# support_mega2560_pro_mini.net
KiCad netlist of a schematic drawn in EasyEDA
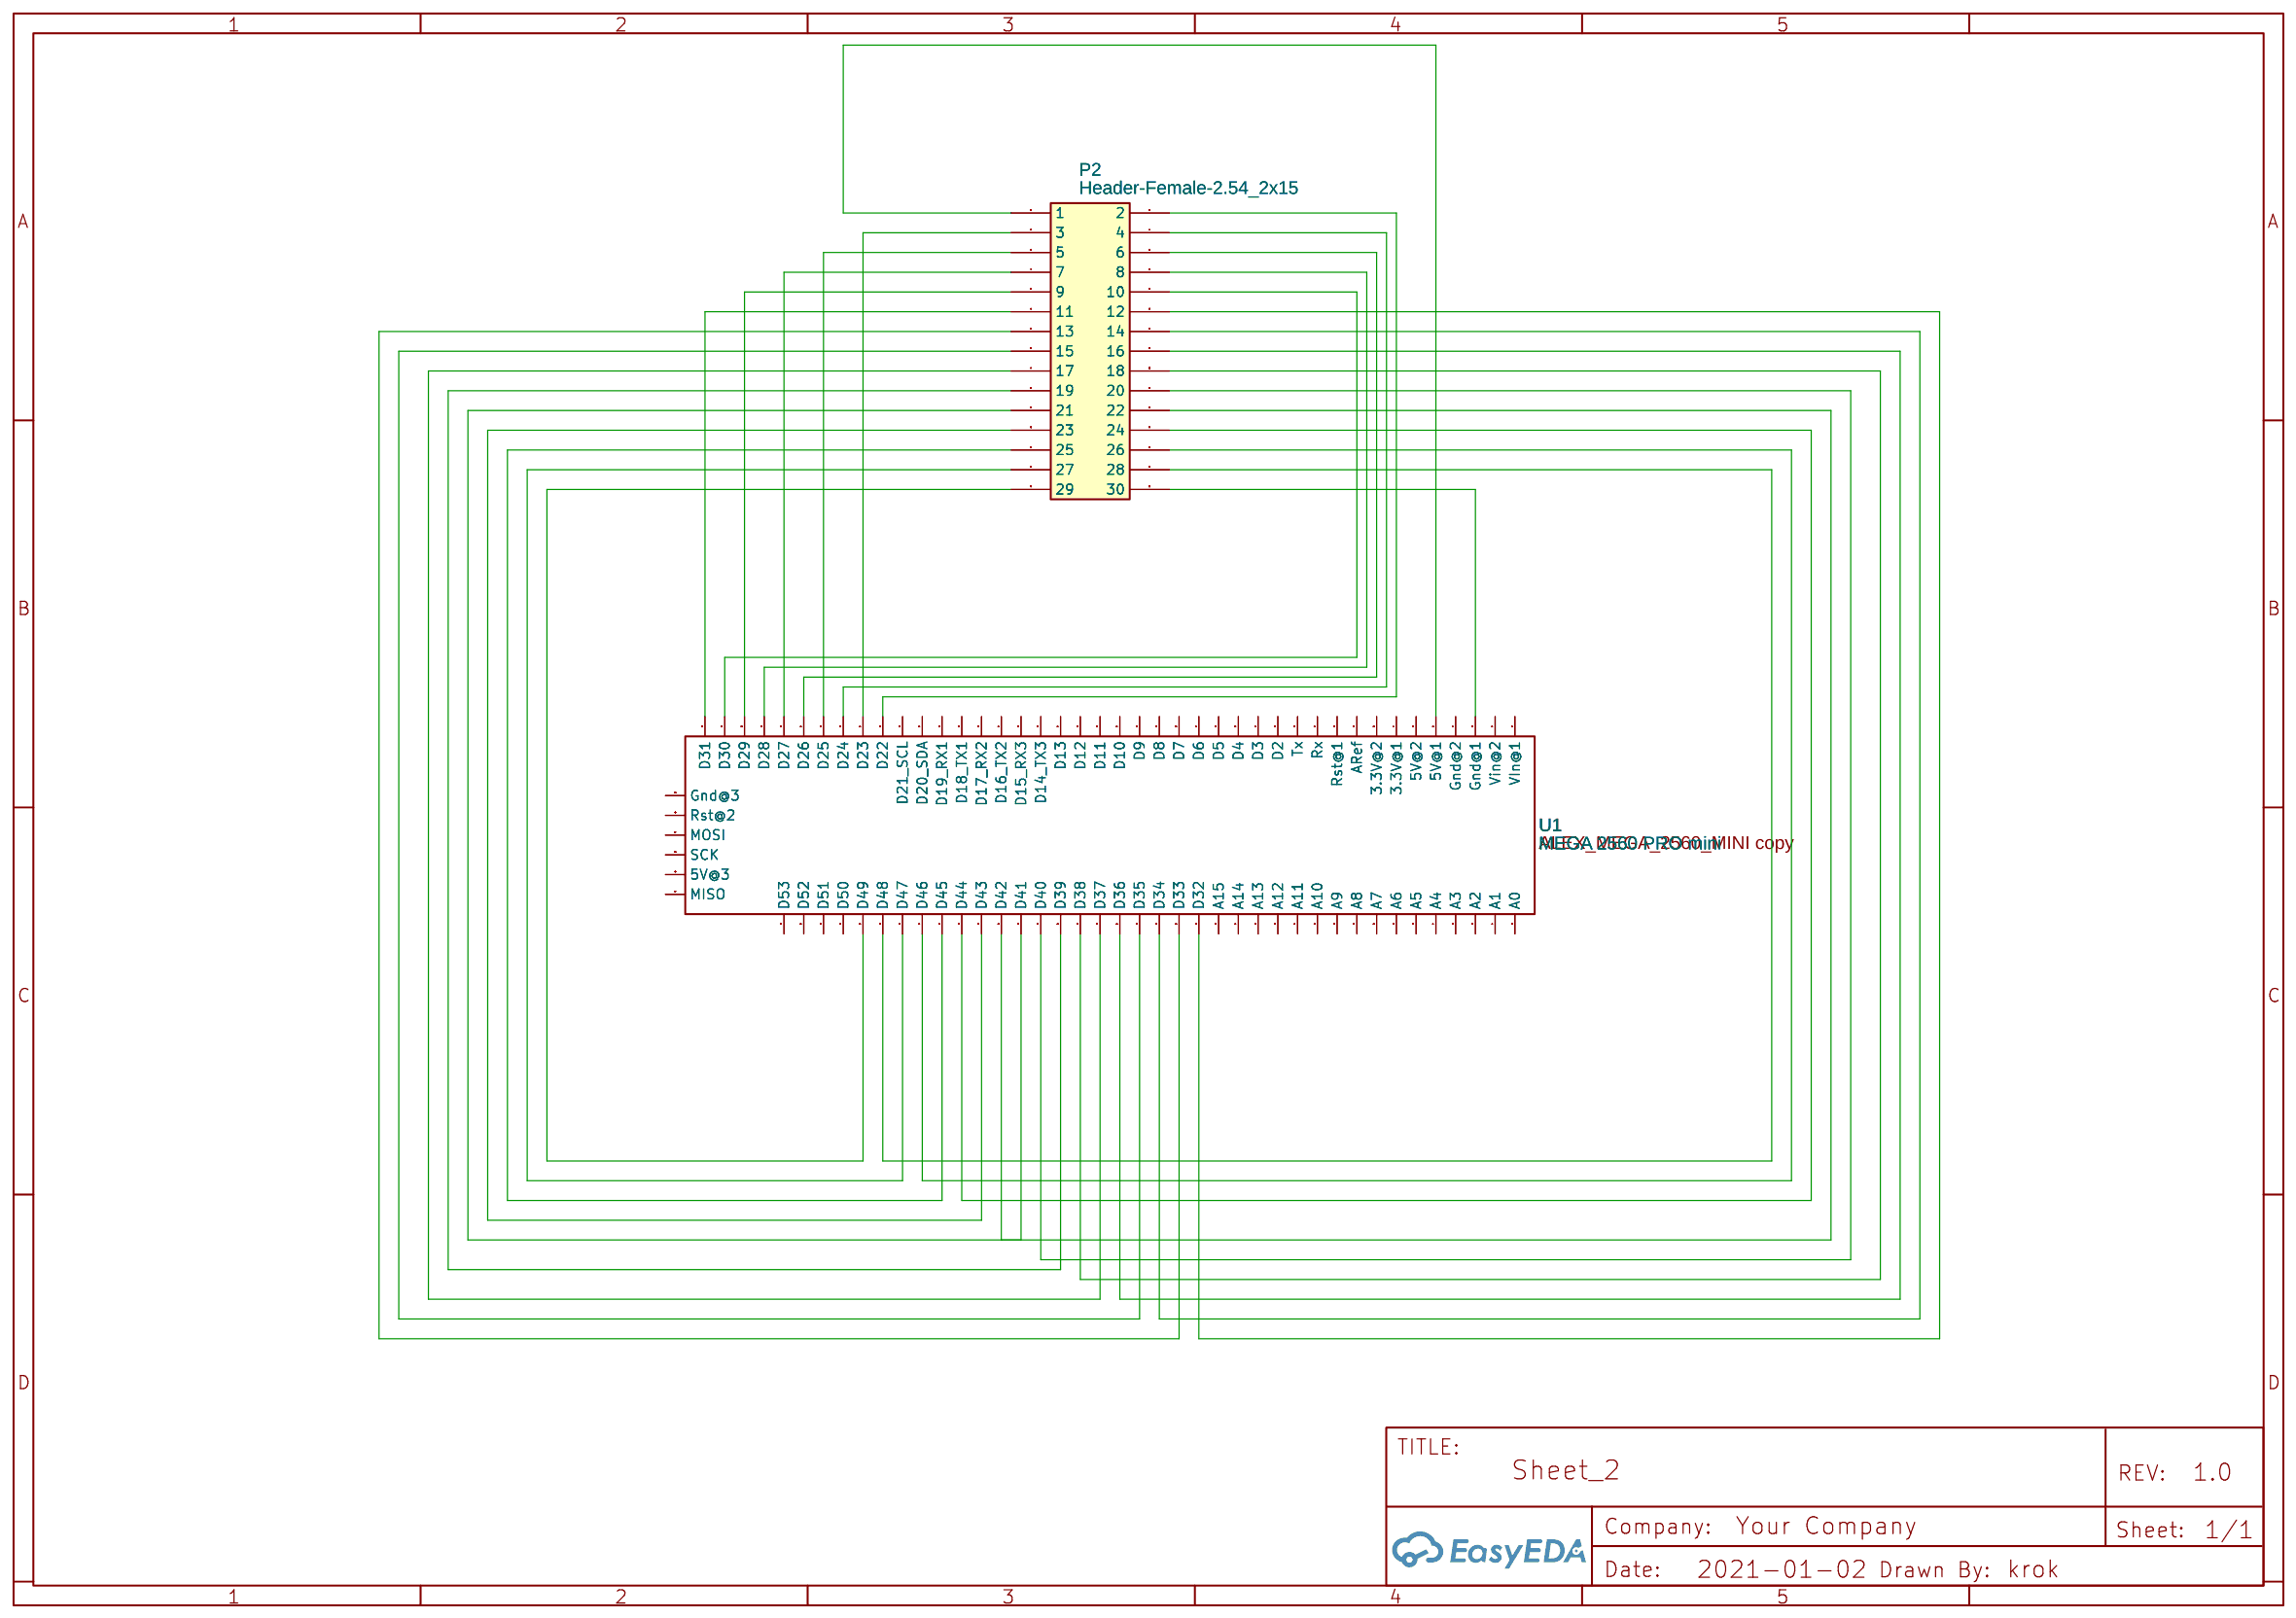
[diagram p0: schematic sheet]

(export (version "E")
  (design (tool "Eeschema 10.0.6"))
  (components
    (comp (ref "P2")
      (value "Header-Female-2.54_2x15")
      (fields (field (name "BOM_Supplier Part") "E58377"))
      (libsource (lib "") (part "Header-Female-2.54_2x15"))
    )
    (comp (ref "U1") (value "MEGA 2560 PRO mini") (libsource (lib "") (part "MEGA 2560 PRO mini")))
  )
  (nets
    (net (code "1") (name "Net-(U1-5V@1)") (class "Default")
      (node (ref "P2") (pin "1") (pinfunction "1_1") (pintype "input"))
      (node (ref "U1") (pin "5") (pinfunction "5V@1_5") (pintype "unspecified"))
    )
    (net (code "2") (name "Net-(U1-D22)") (class "Default")
      (node (ref "P2") (pin "2") (pinfunction "2_2") (pintype "input"))
      (node (ref "U1") (pin "33") (pinfunction "D22_33") (pintype "unspecified"))
    )
    (net (code "3") (name "Net-(U1-D23)") (class "Default")
      (node (ref "P2") (pin "3") (pinfunction "3_3") (pintype "input"))
      (node (ref "U1") (pin "34") (pinfunction "D23_34") (pintype "unspecified"))
    )
    (net (code "4") (name "Net-(U1-D24)") (class "Default")
      (node (ref "P2") (pin "4") (pinfunction "4_4") (pintype "input"))
      (node (ref "U1") (pin "35") (pinfunction "D24_35") (pintype "unspecified"))
    )
    (net (code "5") (name "Net-(U1-D25)") (class "Default")
      (node (ref "P2") (pin "5") (pinfunction "5_5") (pintype "input"))
      (node (ref "U1") (pin "36") (pinfunction "D25_36") (pintype "unspecified"))
    )
    (net (code "6") (name "Net-(U1-D26)") (class "Default")
      (node (ref "P2") (pin "6") (pinfunction "6_6") (pintype "input"))
      (node (ref "U1") (pin "37") (pinfunction "D26_37") (pintype "unspecified"))
    )
    (net (code "7") (name "Net-(U1-D27)") (class "Default")
      (node (ref "P2") (pin "7") (pinfunction "7_7") (pintype "input"))
      (node (ref "U1") (pin "38") (pinfunction "D27_38") (pintype "unspecified"))
    )
    (net (code "8") (name "Net-(U1-D28)") (class "Default")
      (node (ref "P2") (pin "8") (pinfunction "8_8") (pintype "input"))
      (node (ref "U1") (pin "39") (pinfunction "D28_39") (pintype "unspecified"))
    )
    (net (code "9") (name "Net-(U1-D29)") (class "Default")
      (node (ref "P2") (pin "9") (pinfunction "9_9") (pintype "input"))
      (node (ref "U1") (pin "40") (pinfunction "D29_40") (pintype "unspecified"))
    )
    (net (code "10") (name "Net-(U1-D30)") (class "Default")
      (node (ref "P2") (pin "10") (pinfunction "10_10") (pintype "input"))
      (node (ref "U1") (pin "41") (pinfunction "D30_41") (pintype "unspecified"))
    )
    (net (code "11") (name "Net-(U1-D31)") (class "Default")
      (node (ref "P2") (pin "11") (pinfunction "11_11") (pintype "input"))
      (node (ref "U1") (pin "42") (pinfunction "D31_42") (pintype "unspecified"))
    )
    (net (code "12") (name "Net-(U1-D32)") (class "Default")
      (node (ref "P2") (pin "12") (pinfunction "12_12") (pintype "input"))
      (node (ref "U1") (pin "59") (pinfunction "D32_59") (pintype "unspecified"))
    )
    (net (code "13") (name "Net-(U1-D33)") (class "Default")
      (node (ref "P2") (pin "13") (pinfunction "13_13") (pintype "input"))
      (node (ref "U1") (pin "60") (pinfunction "D33_60") (pintype "unspecified"))
    )
    (net (code "14") (name "Net-(U1-D34)") (class "Default")
      (node (ref "P2") (pin "14") (pinfunction "14_14") (pintype "input"))
      (node (ref "U1") (pin "61") (pinfunction "D34_61") (pintype "unspecified"))
    )
    (net (code "15") (name "Net-(U1-D35)") (class "Default")
      (node (ref "P2") (pin "15") (pinfunction "15_15") (pintype "input"))
      (node (ref "U1") (pin "62") (pinfunction "D35_62") (pintype "unspecified"))
    )
    (net (code "16") (name "Net-(U1-D36)") (class "Default")
      (node (ref "P2") (pin "16") (pinfunction "16_16") (pintype "input"))
      (node (ref "U1") (pin "63") (pinfunction "D36_63") (pintype "unspecified"))
    )
    (net (code "17") (name "Net-(U1-D37)") (class "Default")
      (node (ref "P2") (pin "17") (pinfunction "17_17") (pintype "input"))
      (node (ref "U1") (pin "64") (pinfunction "D37_64") (pintype "unspecified"))
    )
    (net (code "18") (name "Net-(U1-D38)") (class "Default")
      (node (ref "P2") (pin "18") (pinfunction "18_18") (pintype "input"))
      (node (ref "U1") (pin "65") (pinfunction "D38_65") (pintype "unspecified"))
    )
    (net (code "19") (name "Net-(U1-D39)") (class "Default")
      (node (ref "P2") (pin "19") (pinfunction "19_19") (pintype "input"))
      (node (ref "U1") (pin "66") (pinfunction "D39_66") (pintype "unspecified"))
    )
    (net (code "20") (name "Net-(U1-D40)") (class "Default")
      (node (ref "P2") (pin "20") (pinfunction "20_20") (pintype "input"))
      (node (ref "U1") (pin "67") (pinfunction "D40_67") (pintype "unspecified"))
    )
    (net (code "21") (name "Net-(U1-D41)") (class "Default")
      (node (ref "P2") (pin "21") (pinfunction "21_21") (pintype "input"))
      (node (ref "U1") (pin "68") (pinfunction "D41_68") (pintype "unspecified"))
    )
    (net (code "22") (name "Net-(U1-D42)") (class "Default")
      (node (ref "P2") (pin "22") (pinfunction "22_22") (pintype "input"))
      (node (ref "U1") (pin "69") (pinfunction "D42_69") (pintype "unspecified"))
    )
    (net (code "23") (name "Net-(U1-D43)") (class "Default")
      (node (ref "P2") (pin "23") (pinfunction "23_23") (pintype "input"))
      (node (ref "U1") (pin "70") (pinfunction "D43_70") (pintype "unspecified"))
    )
    (net (code "24") (name "Net-(U1-D44)") (class "Default")
      (node (ref "P2") (pin "24") (pinfunction "24_24") (pintype "input"))
      (node (ref "U1") (pin "71") (pinfunction "D44_71") (pintype "unspecified"))
    )
    (net (code "25") (name "Net-(U1-D45)") (class "Default")
      (node (ref "P2") (pin "25") (pinfunction "25_25") (pintype "input"))
      (node (ref "U1") (pin "72") (pinfunction "D45_72") (pintype "unspecified"))
    )
    (net (code "26") (name "Net-(U1-D46)") (class "Default")
      (node (ref "P2") (pin "26") (pinfunction "26_26") (pintype "input"))
      (node (ref "U1") (pin "73") (pinfunction "D46_73") (pintype "unspecified"))
    )
    (net (code "27") (name "Net-(U1-D47)") (class "Default")
      (node (ref "P2") (pin "27") (pinfunction "27_27") (pintype "input"))
      (node (ref "U1") (pin "74") (pinfunction "D47_74") (pintype "unspecified"))
    )
    (net (code "28") (name "Net-(U1-D48)") (class "Default")
      (node (ref "P2") (pin "28") (pinfunction "28_28") (pintype "input"))
      (node (ref "U1") (pin "75") (pinfunction "D48_75") (pintype "unspecified"))
    )
    (net (code "29") (name "Net-(U1-D49)") (class "Default")
      (node (ref "P2") (pin "29") (pinfunction "29_29") (pintype "input"))
      (node (ref "U1") (pin "76") (pinfunction "D49_76") (pintype "unspecified"))
    )
    (net (code "30") (name "Net-(U1-Gnd@1)") (class "Default")
      (node (ref "P2") (pin "30") (pinfunction "30_30") (pintype "input"))
      (node (ref "U1") (pin "3") (pinfunction "Gnd@1_3") (pintype "unspecified"))
    )
    (net (code "31") (name "unconnected-(U1-3.3V@1-Pad7)") (class "Default")
      (node (ref "U1") (pin "7") (pinfunction "3.3V@1_7") (pintype "unspecified"))
    )
    (net (code "32") (name "unconnected-(U1-3.3V@2-Pad8)") (class "Default")
      (node (ref "U1") (pin "8") (pinfunction "3.3V@2_8") (pintype "unspecified"))
    )
    (net (code "33") (name "unconnected-(U1-5V@2-Pad6)") (class "Default")
      (node (ref "U1") (pin "6") (pinfunction "5V@2_6") (pintype "unspecified"))
    )
    (net (code "34") (name "unconnected-(U1-5V@3-Pad82)") (class "Default")
      (node (ref "U1") (pin "82") (pinfunction "5V@3_82") (pintype "unspecified"))
    )
    (net (code "35") (name "unconnected-(U1-A0-Pad43)") (class "Default")
      (node (ref "U1") (pin "43") (pinfunction "A0_43") (pintype "unspecified"))
    )
    (net (code "36") (name "unconnected-(U1-A1-Pad44)") (class "Default")
      (node (ref "U1") (pin "44") (pinfunction "A1_44") (pintype "unspecified"))
    )
    (net (code "37") (name "unconnected-(U1-A2-Pad45)") (class "Default")
      (node (ref "U1") (pin "45") (pinfunction "A2_45") (pintype "unspecified"))
    )
    (net (code "38") (name "unconnected-(U1-A3-Pad46)") (class "Default")
      (node (ref "U1") (pin "46") (pinfunction "A3_46") (pintype "unspecified"))
    )
    (net (code "39") (name "unconnected-(U1-A4-Pad47)") (class "Default")
      (node (ref "U1") (pin "47") (pinfunction "A4_47") (pintype "unspecified"))
    )
    (net (code "40") (name "unconnected-(U1-A5-Pad48)") (class "Default")
      (node (ref "U1") (pin "48") (pinfunction "A5_48") (pintype "unspecified"))
    )
    (net (code "41") (name "unconnected-(U1-A6-Pad49)") (class "Default")
      (node (ref "U1") (pin "49") (pinfunction "A6_49") (pintype "unspecified"))
    )
    (net (code "42") (name "unconnected-(U1-A7-Pad50)") (class "Default")
      (node (ref "U1") (pin "50") (pinfunction "A7_50") (pintype "unspecified"))
    )
    (net (code "43") (name "unconnected-(U1-A8-Pad51)") (class "Default")
      (node (ref "U1") (pin "51") (pinfunction "A8_51") (pintype "unspecified"))
    )
    (net (code "44") (name "unconnected-(U1-A9-Pad52)") (class "Default")
      (node (ref "U1") (pin "52") (pinfunction "A9_52") (pintype "unspecified"))
    )
    (net (code "45") (name "unconnected-(U1-A10-Pad53)") (class "Default")
      (node (ref "U1") (pin "53") (pinfunction "A10_53") (pintype "unspecified"))
    )
    (net (code "46") (name "unconnected-(U1-A11-Pad54)") (class "Default")
      (node (ref "U1") (pin "54") (pinfunction "A11_54") (pintype "unspecified"))
    )
    (net (code "47") (name "unconnected-(U1-A12-Pad55)") (class "Default")
      (node (ref "U1") (pin "55") (pinfunction "A12_55") (pintype "unspecified"))
    )
    (net (code "48") (name "unconnected-(U1-A13-Pad56)") (class "Default")
      (node (ref "U1") (pin "56") (pinfunction "A13_56") (pintype "unspecified"))
    )
    (net (code "49") (name "unconnected-(U1-A14-Pad57)") (class "Default")
      (node (ref "U1") (pin "57") (pinfunction "A14_57") (pintype "unspecified"))
    )
    (net (code "50") (name "unconnected-(U1-A15-Pad58)") (class "Default")
      (node (ref "U1") (pin "58") (pinfunction "A15_58") (pintype "unspecified"))
    )
    (net (code "51") (name "unconnected-(U1-ARef-Pad9)") (class "Default")
      (node (ref "U1") (pin "9") (pinfunction "ARef_9") (pintype "unspecified"))
    )
    (net (code "52") (name "unconnected-(U1-D2-Pad13)") (class "Default")
      (node (ref "U1") (pin "13") (pinfunction "D2_13") (pintype "unspecified"))
    )
    (net (code "53") (name "unconnected-(U1-D3-Pad14)") (class "Default")
      (node (ref "U1") (pin "14") (pinfunction "D3_14") (pintype "unspecified"))
    )
    (net (code "54") (name "unconnected-(U1-D4-Pad15)") (class "Default")
      (node (ref "U1") (pin "15") (pinfunction "D4_15") (pintype "unspecified"))
    )
    (net (code "55") (name "unconnected-(U1-D5-Pad16)") (class "Default")
      (node (ref "U1") (pin "16") (pinfunction "D5_16") (pintype "unspecified"))
    )
    (net (code "56") (name "unconnected-(U1-D6-Pad17)") (class "Default")
      (node (ref "U1") (pin "17") (pinfunction "D6_17") (pintype "unspecified"))
    )
    (net (code "57") (name "unconnected-(U1-D7-Pad18)") (class "Default")
      (node (ref "U1") (pin "18") (pinfunction "D7_18") (pintype "unspecified"))
    )
    (net (code "58") (name "unconnected-(U1-D8-Pad19)") (class "Default")
      (node (ref "U1") (pin "19") (pinfunction "D8_19") (pintype "unspecified"))
    )
    (net (code "59") (name "unconnected-(U1-D9-Pad20)") (class "Default")
      (node (ref "U1") (pin "20") (pinfunction "D9_20") (pintype "unspecified"))
    )
    (net (code "60") (name "unconnected-(U1-D10-Pad21)") (class "Default")
      (node (ref "U1") (pin "21") (pinfunction "D10_21") (pintype "unspecified"))
    )
    (net (code "61") (name "unconnected-(U1-D11-Pad22)") (class "Default")
      (node (ref "U1") (pin "22") (pinfunction "D11_22") (pintype "unspecified"))
    )
    (net (code "62") (name "unconnected-(U1-D12-Pad23)") (class "Default")
      (node (ref "U1") (pin "23") (pinfunction "D12_23") (pintype "unspecified"))
    )
    (net (code "63") (name "unconnected-(U1-D13-Pad24)") (class "Default")
      (node (ref "U1") (pin "24") (pinfunction "D13_24") (pintype "unspecified"))
    )
    (net (code "64") (name "unconnected-(U1-D14_TX3-Pad25)") (class "Default")
      (node (ref "U1") (pin "25") (pinfunction "D14_TX3_25") (pintype "unspecified"))
    )
    (net (code "65") (name "unconnected-(U1-D15_RX3-Pad26)") (class "Default")
      (node (ref "U1") (pin "26") (pinfunction "D15_RX3_26") (pintype "unspecified"))
    )
    (net (code "66") (name "unconnected-(U1-D16_TX2-Pad27)") (class "Default")
      (node (ref "U1") (pin "27") (pinfunction "D16_TX2_27") (pintype "unspecified"))
    )
    (net (code "67") (name "unconnected-(U1-D17_RX2-Pad28)") (class "Default")
      (node (ref "U1") (pin "28") (pinfunction "D17_RX2_28") (pintype "unspecified"))
    )
    (net (code "68") (name "unconnected-(U1-D18_TX1-Pad29)") (class "Default")
      (node (ref "U1") (pin "29") (pinfunction "D18_TX1_29") (pintype "unspecified"))
    )
    (net (code "69") (name "unconnected-(U1-D19_RX1-Pad30)") (class "Default")
      (node (ref "U1") (pin "30") (pinfunction "D19_RX1_30") (pintype "unspecified"))
    )
    (net (code "70") (name "unconnected-(U1-D20_SDA-Pad31)") (class "Default")
      (node (ref "U1") (pin "31") (pinfunction "D20_SDA_31") (pintype "unspecified"))
    )
    (net (code "71") (name "unconnected-(U1-D21_SCL-Pad32)") (class "Default")
      (node (ref "U1") (pin "32") (pinfunction "D21_SCL_32") (pintype "unspecified"))
    )
    (net (code "72") (name "unconnected-(U1-D50-Pad77)") (class "Default")
      (node (ref "U1") (pin "77") (pinfunction "D50_77") (pintype "unspecified"))
    )
    (net (code "73") (name "unconnected-(U1-D51-Pad78)") (class "Default")
      (node (ref "U1") (pin "78") (pinfunction "D51_78") (pintype "unspecified"))
    )
    (net (code "74") (name "unconnected-(U1-D52-Pad79)") (class "Default")
      (node (ref "U1") (pin "79") (pinfunction "D52_79") (pintype "unspecified"))
    )
    (net (code "75") (name "unconnected-(U1-D53-Pad80)") (class "Default")
      (node (ref "U1") (pin "80") (pinfunction "D53_80") (pintype "unspecified"))
    )
    (net (code "76") (name "unconnected-(U1-Gnd@2-Pad4)") (class "Default")
      (node (ref "U1") (pin "4") (pinfunction "Gnd@2_4") (pintype "unspecified"))
    )
    (net (code "77") (name "unconnected-(U1-Gnd@3-Pad86)") (class "Default")
      (node (ref "U1") (pin "86") (pinfunction "Gnd@3_86") (pintype "unspecified"))
    )
    (net (code "78") (name "unconnected-(U1-MISO-Pad81)") (class "Default")
      (node (ref "U1") (pin "81") (pinfunction "MISO_81") (pintype "unspecified"))
    )
    (net (code "79") (name "unconnected-(U1-MOSI-Pad84)") (class "Default")
      (node (ref "U1") (pin "84") (pinfunction "MOSI_84") (pintype "unspecified"))
    )
    (net (code "80") (name "unconnected-(U1-Rst@1-Pad10)") (class "Default")
      (node (ref "U1") (pin "10") (pinfunction "Rst@1_10") (pintype "unspecified"))
    )
    (net (code "81") (name "unconnected-(U1-Rst@2-Pad85)") (class "Default")
      (node (ref "U1") (pin "85") (pinfunction "Rst@2_85") (pintype "unspecified"))
    )
    (net (code "82") (name "unconnected-(U1-Rx-Pad11)") (class "Default")
      (node (ref "U1") (pin "11") (pinfunction "Rx_11") (pintype "unspecified"))
    )
    (net (code "83") (name "unconnected-(U1-SCK-Pad83)") (class "Default")
      (node (ref "U1") (pin "83") (pinfunction "SCK_83") (pintype "unspecified"))
    )
    (net (code "84") (name "unconnected-(U1-Tx-Pad12)") (class "Default")
      (node (ref "U1") (pin "12") (pinfunction "Tx_12") (pintype "unspecified"))
    )
    (net (code "85") (name "unconnected-(U1-VIn@1-Pad1)") (class "Default")
      (node (ref "U1") (pin "1") (pinfunction "VIn@1_1") (pintype "unspecified"))
    )
    (net (code "86") (name "unconnected-(U1-Vin@2-Pad2)") (class "Default")
      (node (ref "U1") (pin "2") (pinfunction "Vin@2_2") (pintype "unspecified"))
    )
  )
)
